# V2_XB24DM_node_doublelayer.net
KiCad netlist of a schematic drawn in EAGLE
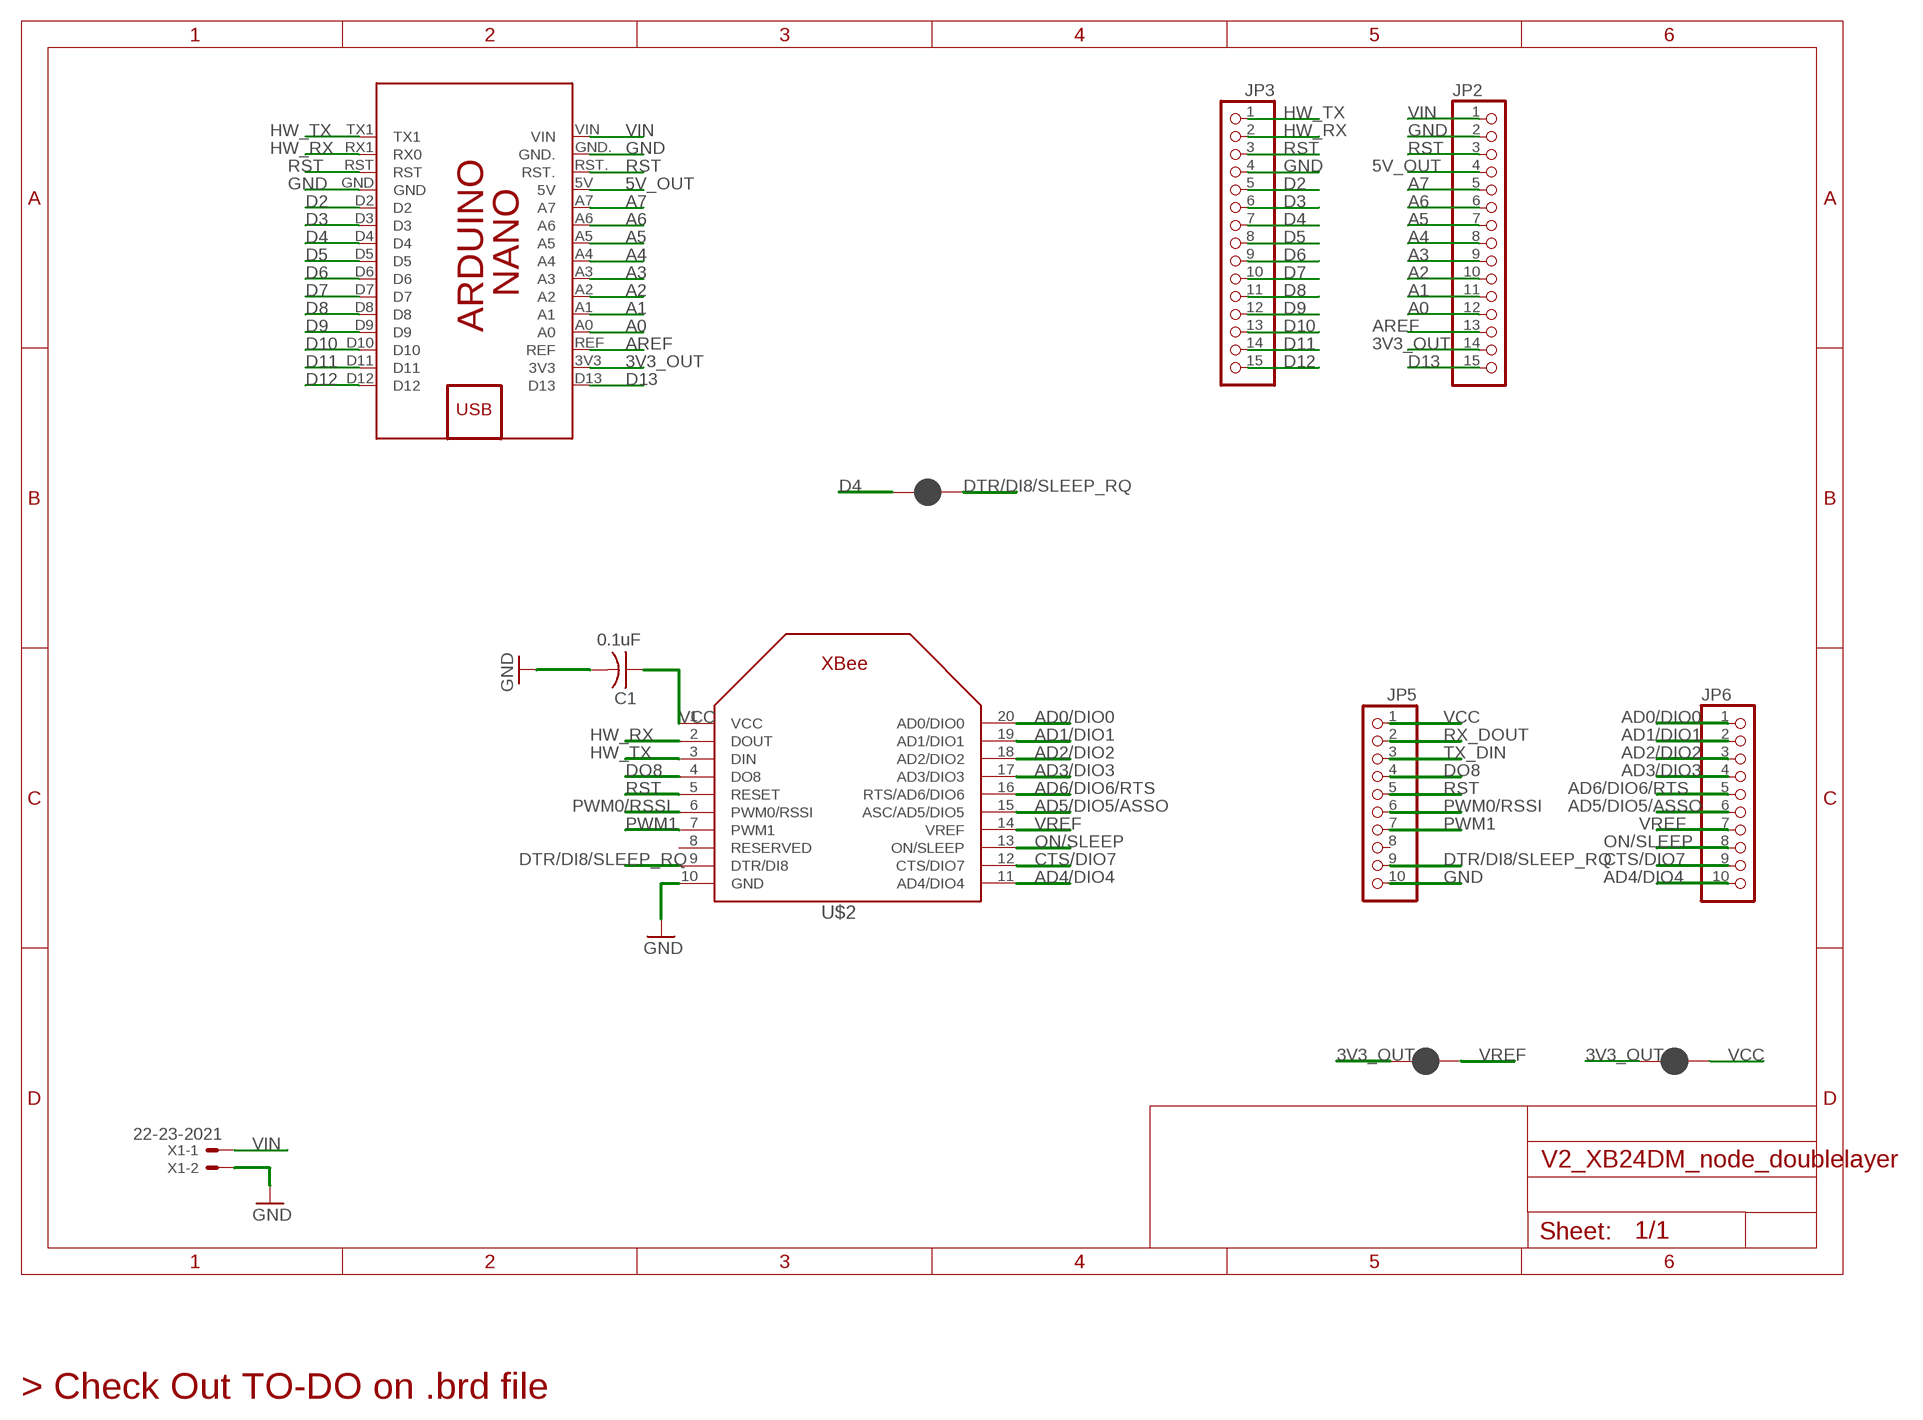
[diagram p0: schematic, sheet 1]

(export (version "E")
  (design (tool "Eeschema 10.0.6"))
  (components
    (comp (ref "C1")
      (value "0.1uF")
      (footprint "eagle-import:C1206")
      (libsource (lib "eagle-import") (part "C-USC1206"))
    )
    (comp (ref "JP1")
      (value "JUMPER-PAD-2-NC_BY_PASTEFULL-BOX-SILK")
      (footprint "eagle-import:PAD-JUMPER-2-NC_BY_PASTE_YES_SILK_FULL_BOX")
      (libsource (lib "eagle-import") (part "JUMPER-PAD-2-NC_BY_PASTEFULL-BOX-SILK"))
    )
    (comp (ref "JP2")
      (value "PINHD-1X15")
      (footprint "eagle-import:1X15")
      (libsource (lib "eagle-import") (part "PINHD-1X15"))
    )
    (comp (ref "JP3")
      (value "PINHD-1X15")
      (footprint "eagle-import:1X15")
      (libsource (lib "eagle-import") (part "PINHD-1X15"))
    )
    (comp (ref "JP4")
      (value "JUMPER-PAD-2-NC_BY_PASTEFULL-BOX-SILK")
      (footprint "eagle-import:PAD-JUMPER-2-NC_BY_PASTE_YES_SILK_FULL_BOX")
      (libsource (lib "eagle-import") (part "JUMPER-PAD-2-NC_BY_PASTEFULL-BOX-SILK"))
    )
    (comp (ref "JP5")
      (value "PINHD-1X10")
      (footprint "eagle-import:1X10")
      (libsource (lib "eagle-import") (part "PINHD-1X10"))
    )
    (comp (ref "JP6")
      (value "PINHD-1X10")
      (footprint "eagle-import:1X10")
      (libsource (lib "eagle-import") (part "PINHD-1X10"))
    )
    (comp (ref "JP7")
      (value "JUMPER-PAD-2-NC_BY_PASTEFULL-BOX-SILK")
      (footprint "eagle-import:PAD-JUMPER-2-NC_BY_PASTE_YES_SILK_FULL_BOX")
      (libsource (lib "eagle-import") (part "JUMPER-PAD-2-NC_BY_PASTEFULL-BOX-SILK"))
    )
    (comp (ref "PCB1")
      (value "ARDUINO_NANO")
      (footprint "eagle-import:ARDUINO_NANO")
      (libsource (lib "eagle-import") (part "ARDUINO_NANO"))
    )
    (comp (ref "U$2")
      (value "XBEE")
      (footprint "eagle-import:XBEE")
      (libsource (lib "eagle-import") (part "XBEE"))
    )
    (comp (ref "X1")
      (value "22-23-2021")
      (footprint "eagle-import:22-23-2021")
      (fields (field (name "MF") "MOLEX"))
      (libsource (lib "eagle-import") (part "22-23-2021"))
    )
  )
  (nets
    (net (code "1") (name "/3V3_OUT") (class "Default")
      (node (ref "JP1") (pin "1") (pinfunction "1_1") (pintype "passive"))
      (node (ref "JP2") (pin "14") (pinfunction "14_14") (pintype "passive"))
      (node (ref "JP7") (pin "1") (pinfunction "1_1") (pintype "passive"))
      (node (ref "PCB1") (pin "3V3") (pinfunction "3V3_3V3") (pintype "bidirectional"))
    )
    (net (code "2") (name "/5V_OUT") (class "Default")
      (node (ref "JP2") (pin "4") (pinfunction "4_4") (pintype "passive"))
      (node (ref "PCB1") (pin "5V") (pinfunction "5V_5V") (pintype "bidirectional"))
    )
    (net (code "3") (name "/A0") (class "Default")
      (node (ref "JP2") (pin "12") (pinfunction "12_12") (pintype "passive"))
      (node (ref "PCB1") (pin "A0") (pinfunction "A0_A0") (pintype "bidirectional"))
    )
    (net (code "4") (name "/A1") (class "Default")
      (node (ref "JP2") (pin "11") (pinfunction "11_11") (pintype "passive"))
      (node (ref "PCB1") (pin "A1") (pinfunction "A1_A1") (pintype "bidirectional"))
    )
    (net (code "5") (name "/A2") (class "Default")
      (node (ref "JP2") (pin "10") (pinfunction "10_10") (pintype "passive"))
      (node (ref "PCB1") (pin "A2") (pinfunction "A2_A2") (pintype "bidirectional"))
    )
    (net (code "6") (name "/A3") (class "Default")
      (node (ref "JP2") (pin "9") (pinfunction "9_9") (pintype "passive"))
      (node (ref "PCB1") (pin "A3") (pinfunction "A3_A3") (pintype "bidirectional"))
    )
    (net (code "7") (name "/A4") (class "Default")
      (node (ref "JP2") (pin "8") (pinfunction "8_8") (pintype "passive"))
      (node (ref "PCB1") (pin "A4") (pinfunction "A4_A4") (pintype "bidirectional"))
    )
    (net (code "8") (name "/A5") (class "Default")
      (node (ref "JP2") (pin "7") (pinfunction "7_7") (pintype "passive"))
      (node (ref "PCB1") (pin "A5") (pinfunction "A5_A5") (pintype "bidirectional"))
    )
    (net (code "9") (name "/A6") (class "Default")
      (node (ref "JP2") (pin "6") (pinfunction "6_6") (pintype "passive"))
      (node (ref "PCB1") (pin "A6") (pinfunction "A6_A6") (pintype "bidirectional"))
    )
    (net (code "10") (name "/A7") (class "Default")
      (node (ref "JP2") (pin "5") (pinfunction "5_5") (pintype "passive"))
      (node (ref "PCB1") (pin "A7") (pinfunction "A7_A7") (pintype "bidirectional"))
    )
    (net (code "11") (name "/AD0{slash}DIO0") (class "Default")
      (node (ref "JP6") (pin "1") (pinfunction "1_1") (pintype "passive"))
      (node (ref "U$2") (pin "20") (pinfunction "AD0/DIO0_20") (pintype "bidirectional"))
    )
    (net (code "12") (name "/AD1{slash}DIO1") (class "Default")
      (node (ref "JP6") (pin "2") (pinfunction "2_2") (pintype "passive"))
      (node (ref "U$2") (pin "19") (pinfunction "AD1/DIO1_19") (pintype "bidirectional"))
    )
    (net (code "13") (name "/AD2{slash}DIO2") (class "Default")
      (node (ref "JP6") (pin "3") (pinfunction "3_3") (pintype "passive"))
      (node (ref "U$2") (pin "18") (pinfunction "AD2/DIO2_18") (pintype "bidirectional"))
    )
    (net (code "14") (name "/AD3{slash}DIO3") (class "Default")
      (node (ref "JP6") (pin "4") (pinfunction "4_4") (pintype "passive"))
      (node (ref "U$2") (pin "17") (pinfunction "AD3/DIO3_17") (pintype "bidirectional"))
    )
    (net (code "15") (name "/AD4{slash}DIO4") (class "Default")
      (node (ref "JP6") (pin "10") (pinfunction "10_10") (pintype "passive"))
      (node (ref "U$2") (pin "11") (pinfunction "AD4/DIO4_11") (pintype "bidirectional"))
    )
    (net (code "16") (name "/AD5{slash}DIO5{slash}ASSO") (class "Default")
      (node (ref "JP6") (pin "6") (pinfunction "6_6") (pintype "passive"))
      (node (ref "U$2") (pin "15") (pinfunction "ASC/AD5/DIO5_15") (pintype "bidirectional"))
    )
    (net (code "17") (name "/AD6{slash}DIO6{slash}RTS") (class "Default")
      (node (ref "JP6") (pin "5") (pinfunction "5_5") (pintype "passive"))
      (node (ref "U$2") (pin "16") (pinfunction "RTS/AD6/DIO6_16") (pintype "bidirectional"))
    )
    (net (code "18") (name "/AREF") (class "Default")
      (node (ref "JP2") (pin "13") (pinfunction "13_13") (pintype "passive"))
      (node (ref "PCB1") (pin "REF") (pinfunction "REF_REF") (pintype "bidirectional"))
    )
    (net (code "19") (name "/CTS{slash}DIO7") (class "Default")
      (node (ref "JP6") (pin "9") (pinfunction "9_9") (pintype "passive"))
      (node (ref "U$2") (pin "12") (pinfunction "CTS/DIO7_12") (pintype "bidirectional"))
    )
    (net (code "20") (name "/D2") (class "Default")
      (node (ref "JP3") (pin "5") (pinfunction "5_5") (pintype "passive"))
      (node (ref "PCB1") (pin "D2") (pinfunction "D2_D2") (pintype "bidirectional"))
    )
    (net (code "21") (name "/D3") (class "Default")
      (node (ref "JP3") (pin "6") (pinfunction "6_6") (pintype "passive"))
      (node (ref "PCB1") (pin "D3") (pinfunction "D3_D3") (pintype "bidirectional"))
    )
    (net (code "22") (name "/D4") (class "Default")
      (node (ref "JP3") (pin "7") (pinfunction "7_7") (pintype "passive"))
      (node (ref "JP4") (pin "1") (pinfunction "1_1") (pintype "passive"))
      (node (ref "PCB1") (pin "D4") (pinfunction "D4_D4") (pintype "bidirectional"))
    )
    (net (code "23") (name "/D5") (class "Default")
      (node (ref "JP3") (pin "8") (pinfunction "8_8") (pintype "passive"))
      (node (ref "PCB1") (pin "D5") (pinfunction "D5_D5") (pintype "bidirectional"))
    )
    (net (code "24") (name "/D6") (class "Default")
      (node (ref "JP3") (pin "9") (pinfunction "9_9") (pintype "passive"))
      (node (ref "PCB1") (pin "D6") (pinfunction "D6_D6") (pintype "bidirectional"))
    )
    (net (code "25") (name "/D7") (class "Default")
      (node (ref "JP3") (pin "10") (pinfunction "10_10") (pintype "passive"))
      (node (ref "PCB1") (pin "D7") (pinfunction "D7_D7") (pintype "bidirectional"))
    )
    (net (code "26") (name "/D8") (class "Default")
      (node (ref "JP3") (pin "11") (pinfunction "11_11") (pintype "passive"))
      (node (ref "PCB1") (pin "D8") (pinfunction "D8_D8") (pintype "bidirectional"))
    )
    (net (code "27") (name "/D9") (class "Default")
      (node (ref "JP3") (pin "12") (pinfunction "12_12") (pintype "passive"))
      (node (ref "PCB1") (pin "D9") (pinfunction "D9_D9") (pintype "bidirectional"))
    )
    (net (code "28") (name "/D10") (class "Default")
      (node (ref "JP3") (pin "13") (pinfunction "13_13") (pintype "passive"))
      (node (ref "PCB1") (pin "D10") (pinfunction "D10_D10") (pintype "bidirectional"))
    )
    (net (code "29") (name "/D11") (class "Default")
      (node (ref "JP3") (pin "14") (pinfunction "14_14") (pintype "passive"))
      (node (ref "PCB1") (pin "D11") (pinfunction "D11_D11") (pintype "bidirectional"))
    )
    (net (code "30") (name "/D12") (class "Default")
      (node (ref "JP3") (pin "15") (pinfunction "15_15") (pintype "passive"))
      (node (ref "PCB1") (pin "D12") (pinfunction "D12_D12") (pintype "bidirectional"))
    )
    (net (code "31") (name "/D13") (class "Default")
      (node (ref "JP2") (pin "15") (pinfunction "15_15") (pintype "passive"))
      (node (ref "PCB1") (pin "D13") (pinfunction "D13_D13") (pintype "bidirectional"))
    )
    (net (code "32") (name "/DO8") (class "Default")
      (node (ref "JP5") (pin "4") (pinfunction "4_4") (pintype "passive"))
      (node (ref "U$2") (pin "4") (pinfunction "DO8_4") (pintype "output"))
    )
    (net (code "33") (name "/DTR{slash}DI8{slash}SLEEP_RQ") (class "Default")
      (node (ref "JP4") (pin "2") (pinfunction "2_2") (pintype "passive"))
      (node (ref "JP5") (pin "9") (pinfunction "9_9") (pintype "passive"))
      (node (ref "U$2") (pin "9") (pinfunction "DTR/DI8_9") (pintype "input"))
    )
    (net (code "34") (name "/HW_RX") (class "Default")
      (node (ref "JP3") (pin "2") (pinfunction "2_2") (pintype "passive"))
      (node (ref "PCB1") (pin "RX1") (pinfunction "RX0_RX1") (pintype "bidirectional"))
      (node (ref "U$2") (pin "2") (pinfunction "DOUT_2") (pintype "output"))
    )
    (net (code "35") (name "/HW_TX") (class "Default")
      (node (ref "JP3") (pin "1") (pinfunction "1_1") (pintype "passive"))
      (node (ref "PCB1") (pin "TX1") (pinfunction "TX1_TX1") (pintype "bidirectional"))
      (node (ref "U$2") (pin "3") (pinfunction "DIN_3") (pintype "input"))
    )
    (net (code "36") (name "/ON{slash}SLEEP") (class "Default")
      (node (ref "JP6") (pin "8") (pinfunction "8_8") (pintype "passive"))
      (node (ref "U$2") (pin "13") (pinfunction "ON/SLEEP_13") (pintype "output"))
    )
    (net (code "37") (name "/PWM0{slash}RSSI") (class "Default")
      (node (ref "JP5") (pin "6") (pinfunction "6_6") (pintype "passive"))
      (node (ref "U$2") (pin "6") (pinfunction "PWM0/RSSI_6") (pintype "output"))
    )
    (net (code "38") (name "/PWM1") (class "Default")
      (node (ref "JP5") (pin "7") (pinfunction "7_7") (pintype "passive"))
      (node (ref "U$2") (pin "7") (pinfunction "PWM1_7") (pintype "output"))
    )
    (net (code "39") (name "/RST") (class "Default")
      (node (ref "JP2") (pin "3") (pinfunction "3_3") (pintype "passive"))
      (node (ref "JP3") (pin "3") (pinfunction "3_3") (pintype "passive"))
      (node (ref "JP5") (pin "5") (pinfunction "5_5") (pintype "passive"))
      (node (ref "PCB1") (pin "RST") (pinfunction "RST_RST") (pintype "bidirectional"))
      (node (ref "PCB1") (pin "RST.") (pinfunction "RST._RST.") (pintype "bidirectional"))
      (node (ref "U$2") (pin "5") (pinfunction "RESET_5") (pintype "input"))
    )
    (net (code "40") (name "/RX_DOUT") (class "Default")
      (node (ref "JP5") (pin "2") (pinfunction "2_2") (pintype "passive"))
    )
    (net (code "41") (name "/TX_DIN") (class "Default")
      (node (ref "JP5") (pin "3") (pinfunction "3_3") (pintype "passive"))
    )
    (net (code "42") (name "/VCC") (class "Default")
      (node (ref "C1") (pin "1") (pinfunction "1_1") (pintype "passive"))
      (node (ref "JP1") (pin "2") (pinfunction "2_2") (pintype "passive"))
      (node (ref "JP5") (pin "1") (pinfunction "1_1") (pintype "passive"))
      (node (ref "U$2") (pin "1") (pinfunction "VCC_1") (pintype "power_in"))
    )
    (net (code "43") (name "/VIN") (class "Default")
      (node (ref "JP2") (pin "1") (pinfunction "1_1") (pintype "passive"))
      (node (ref "PCB1") (pin "VIN") (pinfunction "VIN_VIN") (pintype "bidirectional"))
      (node (ref "X1") (pin "1") (pinfunction "S_1") (pintype "passive"))
    )
    (net (code "44") (name "/VREF") (class "Default")
      (node (ref "JP6") (pin "7") (pinfunction "7_7") (pintype "passive"))
      (node (ref "JP7") (pin "2") (pinfunction "2_2") (pintype "passive"))
      (node (ref "U$2") (pin "14") (pinfunction "VREF_14") (pintype "input"))
    )
    (net (code "45") (name "GND") (class "Default")
      (node (ref "C1") (pin "2") (pinfunction "2_2") (pintype "passive"))
      (node (ref "JP2") (pin "2") (pinfunction "2_2") (pintype "passive"))
      (node (ref "JP3") (pin "4") (pinfunction "4_4") (pintype "passive"))
      (node (ref "JP5") (pin "10") (pinfunction "10_10") (pintype "passive"))
      (node (ref "PCB1") (pin "GND") (pinfunction "GND_GND") (pintype "bidirectional"))
      (node (ref "PCB1") (pin "GND.") (pinfunction "GND._GND.") (pintype "bidirectional"))
      (node (ref "U$2") (pin "10") (pinfunction "GND_10") (pintype "power_in"))
      (node (ref "X1") (pin "2") (pinfunction "S_2") (pintype "passive"))
    )
    (net (code "46") (name "unconnected-(JP5-Pad8)") (class "Default")
      (node (ref "JP5") (pin "8") (pinfunction "8_8") (pintype "passive"))
    )
    (net (code "47") (name "unconnected-(U$2-RESERVED-Pad8)") (class "Default")
      (node (ref "U$2") (pin "8") (pinfunction "RESERVED_8") (pintype "no_connect"))
    )
  )
)
